# Phaser.net
KiCad netlist of a schematic drawn in Altium Designer
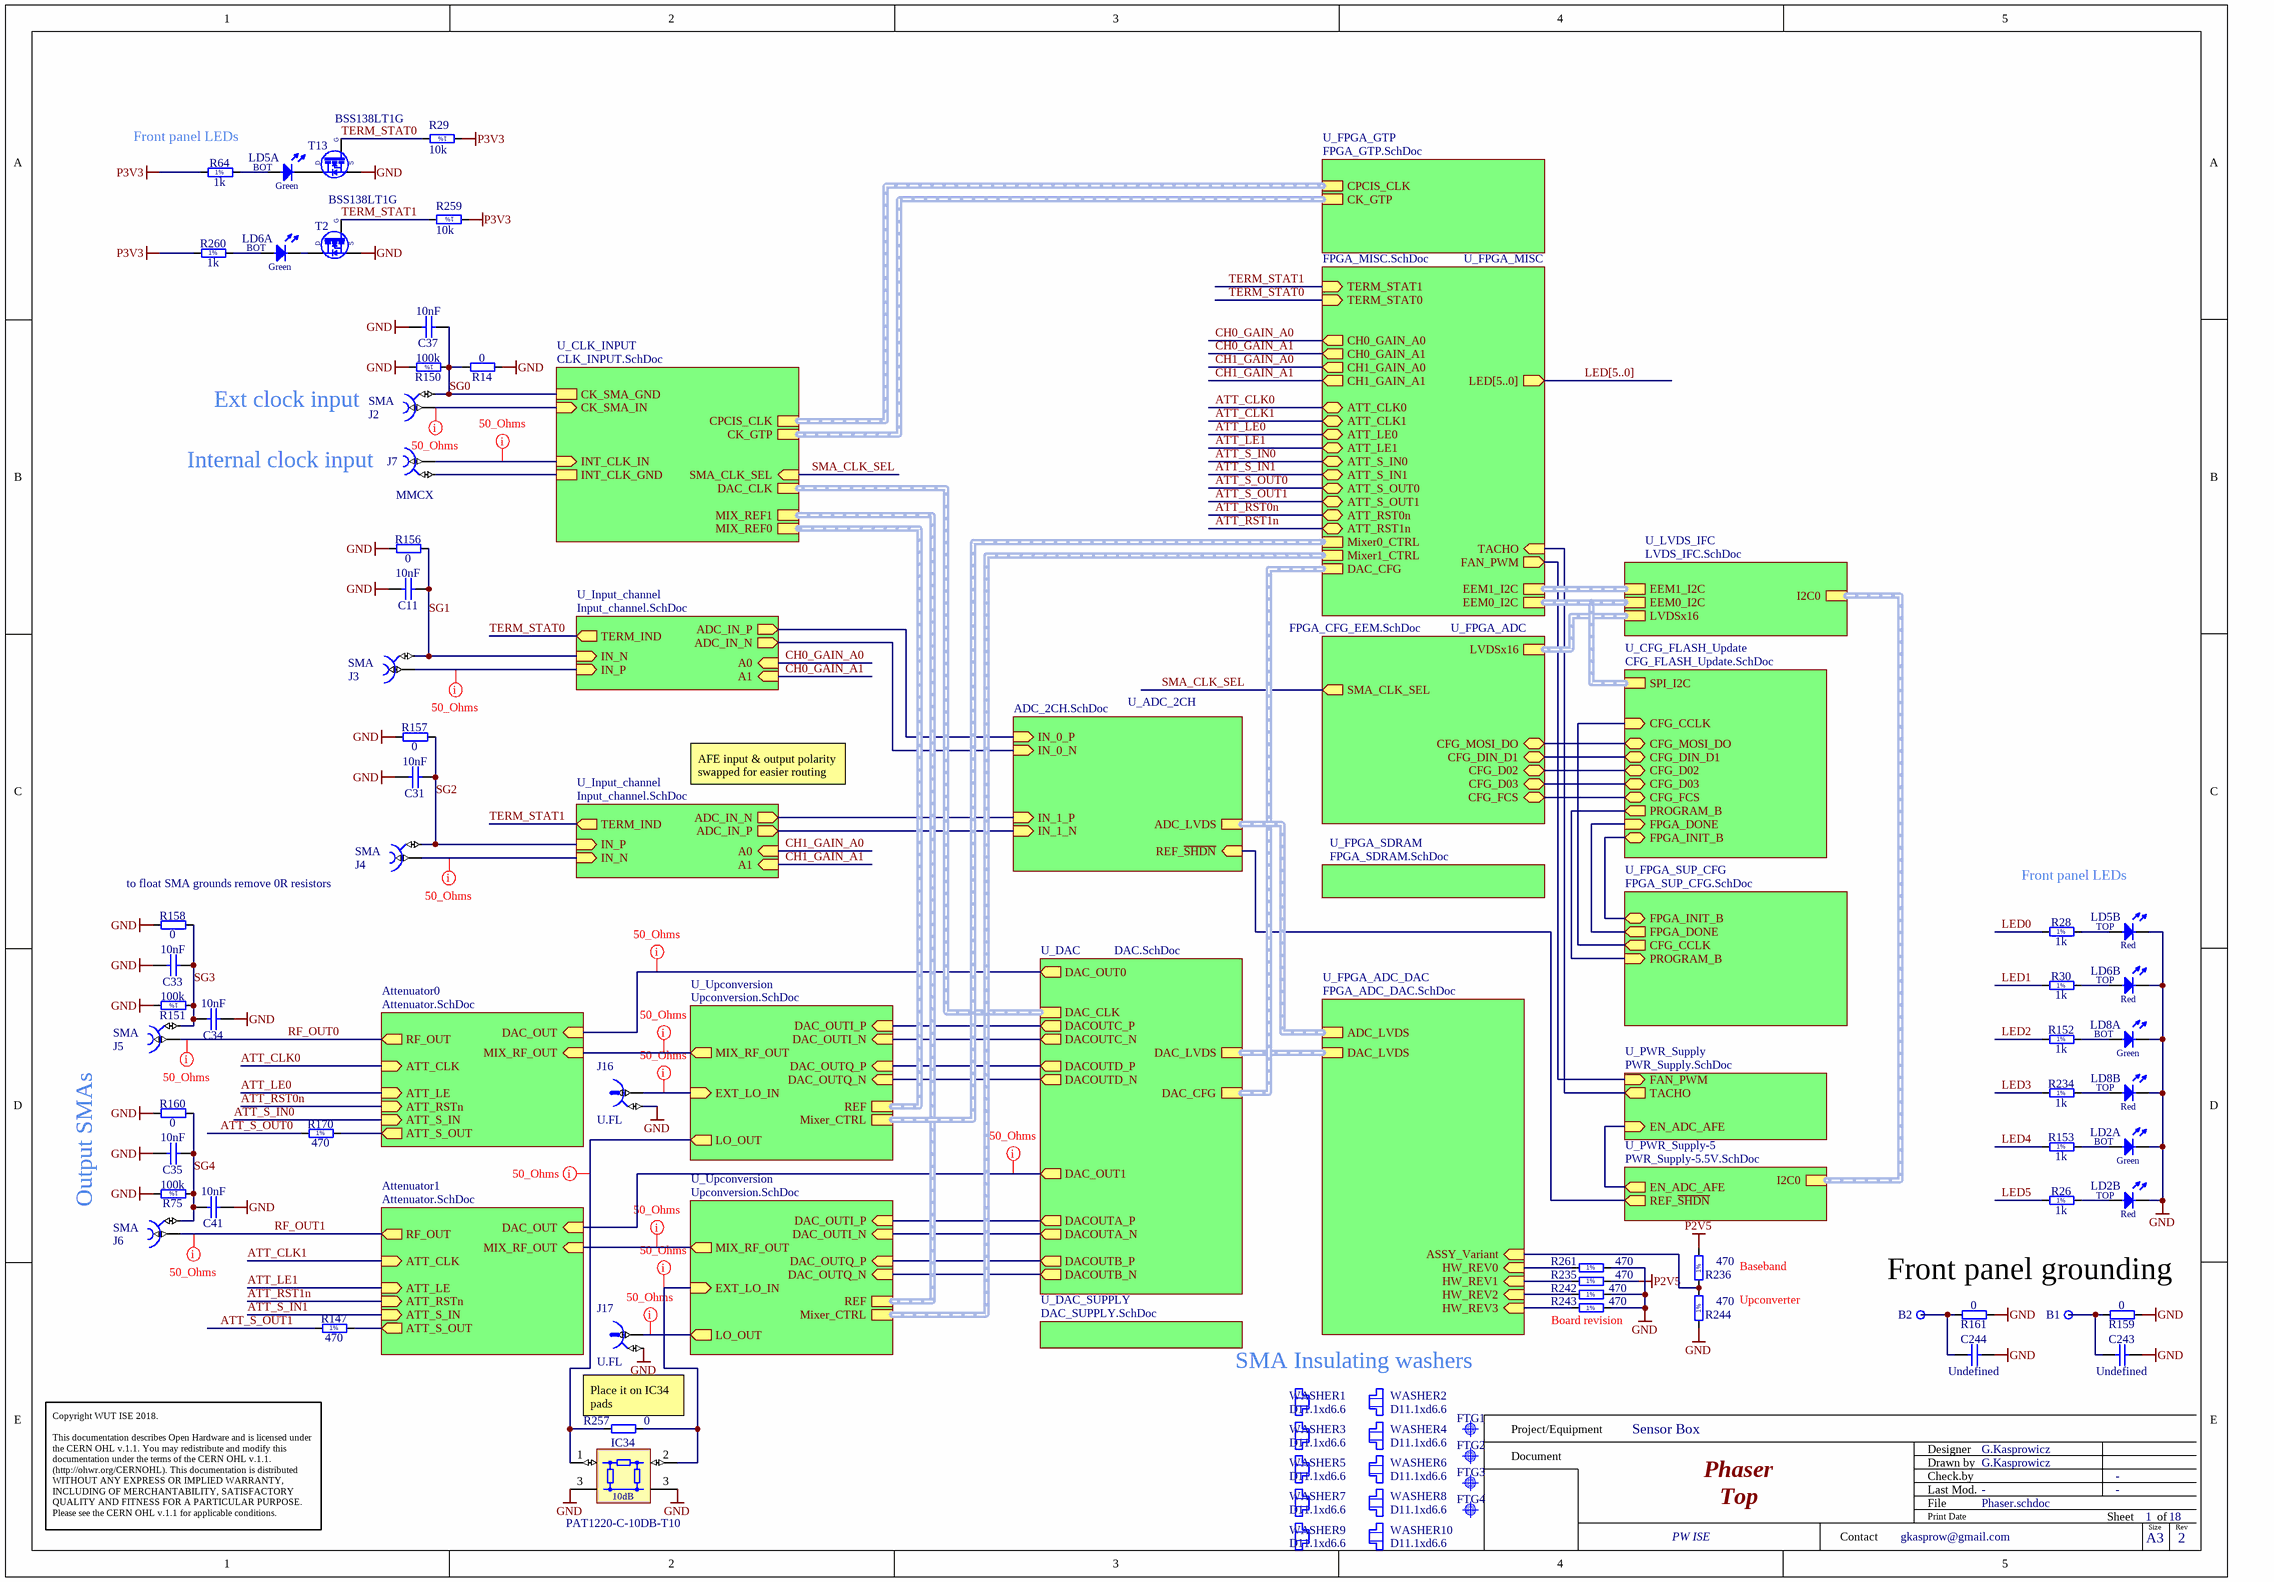
[diagram p0: Phaser.schdoc]

(export (version "E")
  (design (tool "Eeschema 10.0.6"))
  (components
    (comp (ref "B1")
      (value "Plated Hole")
      (footprint "MTG270_500")
      (description "Single Terminal Socket")
      (fields (field (name "PART NUMBER") "PLATED_HOLE2.7_PAD5.0") (field (name "AUTHOR") "CERN DEM JMW"))
      (libsource (lib "Eletro-mechanical") (part "Single Terminal Socket"))
    )
    (comp (ref "B2")
      (value "Plated Hole")
      (footprint "MTG270_500")
      (description "Single Terminal Socket")
      (fields (field (name "PART NUMBER") "PLATED_HOLE2.7_PAD5.0") (field (name "AUTHOR") "CERN DEM JMW"))
      (libsource (lib "Eletro-mechanical") (part "Single Terminal Socket"))
    )
    (comp (ref "C11")
      (value "10nF")
      (footprint "CAPC1005X55N")
      (description "Non-polarised capacitor")
      (fields
        (field (name "PART NUMBER") "CC0402_10NF_16V_10%_X7R")
        (field (name "VOLTAGE") "16V")
        (field (name "AUTHOR") "CERN DEM JLC")
      )
      (libsource (lib "Capacitors") (part "Capacitor - non polarized"))
    )
    (comp (ref "C31")
      (value "10nF")
      (footprint "CAPC1005X55N")
      (description "Non-polarised capacitor")
      (fields
        (field (name "PART NUMBER") "CC0402_10NF_16V_10%_X7R")
        (field (name "VOLTAGE") "16V")
        (field (name "AUTHOR") "CERN DEM JLC")
      )
      (libsource (lib "Capacitors") (part "Capacitor - non polarized"))
    )
    (comp (ref "C33")
      (value "10nF")
      (footprint "CAPC1005X55N")
      (description "Non-polarised capacitor")
      (fields
        (field (name "PART NUMBER") "CC0402_10NF_16V_10%_X7R")
        (field (name "VOLTAGE") "16V")
        (field (name "AUTHOR") "CERN DEM JLC")
      )
      (libsource (lib "Capacitors") (part "Capacitor - non polarized"))
    )
    (comp (ref "C34")
      (value "10nF")
      (footprint "CAPC1005X55N")
      (description "Non-polarised capacitor")
      (fields
        (field (name "PART NUMBER") "CC0402_10NF_16V_10%_X7R")
        (field (name "VOLTAGE") "16V")
        (field (name "AUTHOR") "CERN DEM JLC")
      )
      (libsource (lib "Capacitors") (part "Capacitor - non polarized"))
    )
    (comp (ref "C35")
      (value "10nF")
      (footprint "CAPC1005X55N")
      (description "Non-polarised capacitor")
      (fields
        (field (name "PART NUMBER") "CC0402_10NF_16V_10%_X7R")
        (field (name "VOLTAGE") "16V")
        (field (name "AUTHOR") "CERN DEM JLC")
      )
      (libsource (lib "Capacitors") (part "Capacitor - non polarized"))
    )
    (comp (ref "C37")
      (value "10nF")
      (footprint "CAPC1005X55N")
      (description "Non-polarised capacitor")
      (fields
        (field (name "PART NUMBER") "CC0402_10NF_16V_10%_X7R")
        (field (name "VOLTAGE") "16V")
        (field (name "AUTHOR") "CERN DEM JLC")
      )
      (libsource (lib "Capacitors") (part "Capacitor - non polarized"))
    )
    (comp (ref "C41")
      (value "10nF")
      (footprint "CAPC1005X55N")
      (description "Non-polarised capacitor")
      (fields
        (field (name "PART NUMBER") "CC0402_10NF_16V_10%_X7R")
        (field (name "VOLTAGE") "16V")
        (field (name "AUTHOR") "CERN DEM JLC")
      )
      (libsource (lib "Capacitors") (part "Capacitor - non polarized"))
    )
    (comp (ref "C243")
      (value "Undefined")
      (footprint "CAPC2012X135N")
      (description "Non-polarised capacitor")
      (fields (field (name "PART NUMBER") "CC0805_NO-VALUE") (field (name "AUTHOR") "CERN DEM JLC"))
      (libsource (lib "Capacitors") (part "Capacitor - non polarized"))
    )
    (comp (ref "C244")
      (value "Undefined")
      (footprint "CAPC2012X135N")
      (description "Non-polarised capacitor")
      (fields (field (name "PART NUMBER") "CC0805_NO-VALUE") (field (name "AUTHOR") "CERN DEM JLC"))
      (libsource (lib "Capacitors") (part "Capacitor - non polarized"))
    )
    (comp (ref "FTG1")
      (value "Use only in PCB")
      (footprint "FIDUCIAL_TOP_C100-200")
      (description "Fiducial Target")
      (fields (field (name "PART NUMBER") "FIDUCIAL_TARGET_C100-200") (field (name "AUTHOR") "CERN DEM JLC"))
      (libsource (lib "Eletro-mechanical") (part "Fiducial Target"))
    )
    (comp (ref "FTG2")
      (value "Use only in PCB")
      (footprint "FIDUCIAL_TOP_S100-200")
      (description "Fiducial Target")
      (fields (field (name "PART NUMBER") "FIDUCIAL_TARGET_S100-200") (field (name "AUTHOR") "CERN DEM JLC"))
      (libsource (lib "Eletro-mechanical") (part "Fiducial Target"))
    )
    (comp (ref "FTG3")
      (value "Use only in PCB")
      (footprint "FIDUCIAL_TOP_S100-200")
      (description "Fiducial Target")
      (fields (field (name "PART NUMBER") "FIDUCIAL_TARGET_S100-200") (field (name "AUTHOR") "CERN DEM JLC"))
      (libsource (lib "Eletro-mechanical") (part "Fiducial Target"))
    )
    (comp (ref "FTG4")
      (value "Use only in PCB")
      (footprint "FIDUCIAL_TOP_S100-200")
      (description "Fiducial Target")
      (fields (field (name "PART NUMBER") "FIDUCIAL_TARGET_S100-200") (field (name "AUTHOR") "CERN DEM JLC"))
      (libsource (lib "Eletro-mechanical") (part "Fiducial Target"))
    )
    (comp (ref "IC34")
      (value "PAT1220-C-10DB-T10")
      (footprint "SUSUMU_PAT1220")
      (description "DC to 10GHz, 100mW, 50 Ohm, 10dB, Precision Chip Attenuator")
      (fields (field (name "MANUFACTURER") "SUSUMU") (field (name "AUTHOR") "CERN DEM MR"))
      (libsource (lib "ICs And Semiconductors") (part "PAT1220-C-10DB"))
    )
    (comp (ref "J2")
      (value "SMA")
      (footprint "AMPHENOL_132203-14")
      (description "50 Ohm Through Hole SMA Right Angle PCB Jack")
      (fields
        (field (name "PART NUMBER") "AMPHENOL_132203-14")
        (field (name "MANUFACTURER") "AMPHENOL")
        (field (name "AUTHOR") "GK")
      )
      (libsource (lib "Connectors") (part "CON_SMA_AMP_132203-14"))
    )
    (comp (ref "J3")
      (value "SMA")
      (footprint "AMPHENOL_132203-14")
      (description "50 Ohm Through Hole SMA Right Angle PCB Jack")
      (fields
        (field (name "PART NUMBER") "AMPHENOL_132203-14")
        (field (name "MANUFACTURER") "AMPHENOL")
        (field (name "AUTHOR") "GK")
      )
      (libsource (lib "Connectors") (part "CON_SMA_AMP_132203-14"))
    )
    (comp (ref "J4")
      (value "SMA")
      (footprint "AMPHENOL_132203-14")
      (description "50 Ohm Through Hole SMA Right Angle PCB Jack")
      (fields
        (field (name "PART NUMBER") "AMPHENOL_132203-14")
        (field (name "MANUFACTURER") "AMPHENOL")
        (field (name "AUTHOR") "GK")
      )
      (libsource (lib "Connectors") (part "CON_SMA_AMP_132203-14"))
    )
    (comp (ref "J5")
      (value "SMA")
      (footprint "AMPHENOL_132203-14")
      (description "50 Ohm Through Hole SMA Right Angle PCB Jack")
      (fields
        (field (name "PART NUMBER") "AMPHENOL_132203-14")
        (field (name "MANUFACTURER") "AMPHENOL")
        (field (name "AUTHOR") "GK")
      )
      (libsource (lib "Connectors") (part "CON_SMA_AMP_132203-14"))
    )
    (comp (ref "J6")
      (value "SMA")
      (footprint "AMPHENOL_132203-14")
      (description "50 Ohm Through Hole SMA Right Angle PCB Jack")
      (fields
        (field (name "PART NUMBER") "AMPHENOL_132203-14")
        (field (name "MANUFACTURER") "AMPHENOL")
        (field (name "AUTHOR") "GK")
      )
      (libsource (lib "Connectors") (part "CON_SMA_AMP_132203-14"))
    )
    (comp (ref "J7")
      (value "MMCX")
      (footprint "SAMTEC_MMCX-J-P-H-ST-TH1")
      (fields
        (field (name "PART NUMBER") "SAMTEC_MMCX-J-P-H-ST-TH1")
        (field (name "MANUFACTURER") "SAMTEC")
        (field (name "MANUFACTURER PART NUMBER") "MMCX-J-P-H-ST-TH1")
        (field (name "AUTHOR") "CERN DEM JLC")
      )
      (libsource (lib "Connectors") (part "Coax_1Female_1Shield"))
    )
    (comp (ref "J16")
      (value "U.FL")
      (footprint "HIROSE_U.FL-R-SMT-1(10)")
      (fields
        (field (name "MANUFACTURER") "HIROSE (HRS)")
        (field (name "MANUFACTURER PART NUMBER") "U.FL-R-SMT-1(10)")
        (field (name "PART NUMBER") "HIROSE_U.FL-R-SMT-1(10)")
        (field (name "AUTHOR") "CERN DEM JLC")
      )
      (libsource (lib "Connectors") (part "Coax_1Male_1Shield"))
    )
    (comp (ref "J17")
      (value "U.FL")
      (footprint "HIROSE_U.FL-R-SMT-1(10)")
      (fields
        (field (name "MANUFACTURER") "HIROSE (HRS)")
        (field (name "MANUFACTURER PART NUMBER") "U.FL-R-SMT-1(10)")
        (field (name "PART NUMBER") "HIROSE_U.FL-R-SMT-1(10)")
        (field (name "AUTHOR") "CERN DEM JLC")
      )
      (libsource (lib "Connectors") (part "Coax_1Male_1Shield"))
    )
    (comp (ref "LD2")
      (value "Red/Green")
      (footprint "LED_DIALIGHT_571-0112F")
      (description "2x LED  Botom Green, Top Red")
      (fields
        (field (name "PART NUMBER") "LED_DIALIGHT_571-0112F")
        (field (name "MANUFACTURER") "DIALIGHT")
        (field (name "AUTHOR") "CERN DEM JLC")
      )
      (libsource (lib "ICs And Semiconductors") (part "LED x2 G-1C2A-BOT_R-3C4A-TOP"))
    )
    (comp (ref "LD5")
      (value "Red/Green")
      (footprint "LED_DIALIGHT_571-0112F")
      (description "2x LED  Botom Green, Top Red")
      (fields
        (field (name "PART NUMBER") "LED_DIALIGHT_571-0112F")
        (field (name "MANUFACTURER") "DIALIGHT")
        (field (name "AUTHOR") "CERN DEM JLC")
      )
      (libsource (lib "ICs And Semiconductors") (part "LED x2 G-1C2A-BOT_R-3C4A-TOP"))
    )
    (comp (ref "LD6")
      (value "Red/Green")
      (footprint "LED_DIALIGHT_571-0112F")
      (description "2x LED  Botom Green, Top Red")
      (fields
        (field (name "PART NUMBER") "LED_DIALIGHT_571-0112F")
        (field (name "MANUFACTURER") "DIALIGHT")
        (field (name "AUTHOR") "CERN DEM JLC")
      )
      (libsource (lib "ICs And Semiconductors") (part "LED x2 G-1C2A-BOT_R-3C4A-TOP"))
    )
    (comp (ref "LD8")
      (value "Red/Green")
      (footprint "LED_DIALIGHT_571-0112F")
      (description "2x LED  Botom Green, Top Red")
      (fields
        (field (name "PART NUMBER") "LED_DIALIGHT_571-0112F")
        (field (name "MANUFACTURER") "DIALIGHT")
        (field (name "AUTHOR") "CERN DEM JLC")
      )
      (libsource (lib "ICs And Semiconductors") (part "LED x2 G-1C2A-BOT_R-3C4A-TOP"))
    )
    (comp (ref "R14")
      (value "0")
      (footprint "RESC1608X55N")
      (description "Resistor")
      (fields
        (field (name "PART NUMBER") "R0603_0R_JUMPER")
        (field (name "MANUFACTURER") "GENERIC")
        (field (name "AUTHOR") "CERN DEM JLC")
      )
      (libsource (lib "Resistors") (part "Resistor"))
    )
    (comp (ref "R26")
      (value "1k")
      (footprint "RESC1005X40N")
      (description "Resistor - 1%")
      (fields
        (field (name "PART NUMBER") "R0402_1K_1%_0.0625W_100PPM")
        (field (name "POWER") "0.0625W")
        (field (name "AUTHOR") "CERN DEM JLC")
      )
      (libsource (lib "Resistors") (part "Resistor - 1%"))
    )
    (comp (ref "R28")
      (value "1k")
      (footprint "RESC1005X40N")
      (description "Resistor - 1%")
      (fields
        (field (name "PART NUMBER") "R0402_1K_1%_0.0625W_100PPM")
        (field (name "POWER") "0.0625W")
        (field (name "AUTHOR") "CERN DEM JLC")
      )
      (libsource (lib "Resistors") (part "Resistor - 1%"))
    )
    (comp (ref "R29")
      (value "10k")
      (footprint "RESC1005X40N")
      (description "Resistor - 1%")
      (fields
        (field (name "PART NUMBER") "R0402_10K_1%_0.0625W_100PPM")
        (field (name "POWER") "0.0625W")
        (field (name "AUTHOR") "CERN DEM JLC")
      )
      (libsource (lib "Resistors") (part "Resistor - 1%"))
    )
    (comp (ref "R30")
      (value "1k")
      (footprint "RESC1005X40N")
      (description "Resistor - 1%")
      (fields
        (field (name "PART NUMBER") "R0402_1K_1%_0.0625W_100PPM")
        (field (name "POWER") "0.0625W")
        (field (name "AUTHOR") "CERN DEM JLC")
      )
      (libsource (lib "Resistors") (part "Resistor - 1%"))
    )
    (comp (ref "R64")
      (value "1k")
      (footprint "RESC1005X40N")
      (description "Resistor - 1%")
      (fields
        (field (name "PART NUMBER") "R0402_1K_1%_0.0625W_100PPM")
        (field (name "POWER") "0.0625W")
        (field (name "AUTHOR") "CERN DEM JLC")
      )
      (libsource (lib "Resistors") (part "Resistor - 1%"))
    )
    (comp (ref "R75")
      (value "100k")
      (footprint "RESC1005X40N")
      (description "Resistor - 1%")
      (fields
        (field (name "PART NUMBER") "R0402_100K_1%_0.0625W_100PPM")
        (field (name "MANUFACTURER") "GENERIC")
        (field (name "AUTHOR") "CERN DEM JLC")
      )
      (libsource (lib "Resistors") (part "Resistor - 1%"))
    )
    (comp (ref "R147")
      (value "470")
      (footprint "RESC1005X40N")
      (description "Resistor - 1%")
      (fields
        (field (name "PART NUMBER") "R0402_470R_1%_0.0625W_100PPM")
        (field (name "POWER") "0.0625W")
        (field (name "AUTHOR") "CERN DEM JLC")
      )
      (libsource (lib "Resistors") (part "Resistor - 1%"))
    )
    (comp (ref "R150")
      (value "100k")
      (footprint "RESC1005X40N")
      (description "Resistor - 1%")
      (fields
        (field (name "PART NUMBER") "R0402_100K_1%_0.0625W_100PPM")
        (field (name "MANUFACTURER") "GENERIC")
        (field (name "AUTHOR") "CERN DEM JLC")
      )
      (libsource (lib "Resistors") (part "Resistor - 1%"))
    )
    (comp (ref "R151")
      (value "100k")
      (footprint "RESC1005X40N")
      (description "Resistor - 1%")
      (fields
        (field (name "PART NUMBER") "R0402_100K_1%_0.0625W_100PPM")
        (field (name "MANUFACTURER") "GENERIC")
        (field (name "AUTHOR") "CERN DEM JLC")
      )
      (libsource (lib "Resistors") (part "Resistor - 1%"))
    )
    (comp (ref "R152")
      (value "1k")
      (footprint "RESC1005X40N")
      (description "Resistor - 1%")
      (fields
        (field (name "PART NUMBER") "R0402_1K_1%_0.0625W_100PPM")
        (field (name "POWER") "0.0625W")
        (field (name "AUTHOR") "CERN DEM JLC")
      )
      (libsource (lib "Resistors") (part "Resistor - 1%"))
    )
    (comp (ref "R153")
      (value "1k")
      (footprint "RESC1005X40N")
      (description "Resistor - 1%")
      (fields
        (field (name "PART NUMBER") "R0402_1K_1%_0.0625W_100PPM")
        (field (name "POWER") "0.0625W")
        (field (name "AUTHOR") "CERN DEM JLC")
      )
      (libsource (lib "Resistors") (part "Resistor - 1%"))
    )
    (comp (ref "R156")
      (value "0")
      (footprint "RESC1608X55N")
      (description "Resistor")
      (fields
        (field (name "PART NUMBER") "R0603_0R_JUMPER")
        (field (name "MANUFACTURER") "GENERIC")
        (field (name "AUTHOR") "CERN DEM JLC")
      )
      (libsource (lib "Resistors") (part "Resistor"))
    )
    (comp (ref "R157")
      (value "0")
      (footprint "RESC1608X55N")
      (description "Resistor")
      (fields
        (field (name "PART NUMBER") "R0603_0R_JUMPER")
        (field (name "MANUFACTURER") "GENERIC")
        (field (name "AUTHOR") "CERN DEM JLC")
      )
      (libsource (lib "Resistors") (part "Resistor"))
    )
    (comp (ref "R158")
      (value "0")
      (footprint "RESC1608X55N")
      (description "Resistor")
      (fields
        (field (name "PART NUMBER") "R0603_0R_JUMPER")
        (field (name "MANUFACTURER") "GENERIC")
        (field (name "AUTHOR") "CERN DEM JLC")
      )
      (libsource (lib "Resistors") (part "Resistor"))
    )
    (comp (ref "R159")
      (value "0")
      (footprint "RESC1608X55N")
      (description "Resistor")
      (fields
        (field (name "PART NUMBER") "R0603_0R_JUMPER")
        (field (name "MANUFACTURER") "GENERIC")
        (field (name "AUTHOR") "CERN DEM JLC")
      )
      (libsource (lib "Resistors") (part "Resistor"))
    )
    (comp (ref "R160")
      (value "0")
      (footprint "RESC1608X55N")
      (description "Resistor")
      (fields
        (field (name "PART NUMBER") "R0603_0R_JUMPER")
        (field (name "MANUFACTURER") "GENERIC")
        (field (name "AUTHOR") "CERN DEM JLC")
      )
      (libsource (lib "Resistors") (part "Resistor"))
    )
    (comp (ref "R161")
      (value "0")
      (footprint "RESC1608X55N")
      (description "Resistor")
      (fields
        (field (name "PART NUMBER") "R0603_0R_JUMPER")
        (field (name "MANUFACTURER") "GENERIC")
        (field (name "AUTHOR") "CERN DEM JLC")
      )
      (libsource (lib "Resistors") (part "Resistor"))
    )
    (comp (ref "R170")
      (value "470")
      (footprint "RESC1005X40N")
      (description "Resistor - 1%")
      (fields
        (field (name "PART NUMBER") "R0402_470R_1%_0.0625W_100PPM")
        (field (name "POWER") "0.0625W")
        (field (name "AUTHOR") "CERN DEM JLC")
      )
      (libsource (lib "Resistors") (part "Resistor - 1%"))
    )
    (comp (ref "R234")
      (value "1k")
      (footprint "RESC1005X40N")
      (description "Resistor - 1%")
      (fields
        (field (name "PART NUMBER") "R0402_1K_1%_0.0625W_100PPM")
        (field (name "POWER") "0.0625W")
        (field (name "AUTHOR") "CERN DEM JLC")
      )
      (libsource (lib "Resistors") (part "Resistor - 1%"))
    )
    (comp (ref "R235")
      (value "470")
      (footprint "RESC1005X40N")
      (description "Resistor - 1%")
      (fields
        (field (name "PART NUMBER") "R0402_470R_1%_0.0625W_100PPM")
        (field (name "POWER") "0.0625W")
        (field (name "AUTHOR") "CERN DEM JLC")
      )
      (libsource (lib "Resistors") (part "Resistor - 1%"))
    )
    (comp (ref "R236")
      (value "470")
      (footprint "RESC1005X40N")
      (description "Resistor - 1%")
      (fields
        (field (name "PART NUMBER") "R0402_470R_1%_0.0625W_100PPM")
        (field (name "POWER") "0.0625W")
        (field (name "AUTHOR") "CERN DEM JLC")
      )
      (libsource (lib "Resistors") (part "Resistor - 1%"))
    )
    (comp (ref "R242")
      (value "470")
      (footprint "RESC1005X40N")
      (description "Resistor - 1%")
      (fields
        (field (name "PART NUMBER") "R0402_470R_1%_0.0625W_100PPM")
        (field (name "POWER") "0.0625W")
        (field (name "AUTHOR") "CERN DEM JLC")
      )
      (libsource (lib "Resistors") (part "Resistor - 1%"))
    )
    (comp (ref "R243")
      (value "470")
      (footprint "RESC1005X40N")
      (description "Resistor - 1%")
      (fields
        (field (name "PART NUMBER") "R0402_470R_1%_0.0625W_100PPM")
        (field (name "POWER") "0.0625W")
        (field (name "AUTHOR") "CERN DEM JLC")
      )
      (libsource (lib "Resistors") (part "Resistor - 1%"))
    )
    (comp (ref "R244")
      (value "470")
      (footprint "RESC1005X40N")
      (description "Resistor - 1%")
      (fields
        (field (name "PART NUMBER") "R0402_470R_1%_0.0625W_100PPM")
        (field (name "POWER") "0.0625W")
        (field (name "AUTHOR") "CERN DEM JLC")
      )
      (libsource (lib "Resistors") (part "Resistor - 1%"))
    )
    (comp (ref "R257")
      (value "0")
      (footprint "RESC1005X40N")
      (description "Resistor")
      (fields
        (field (name "PART NUMBER") "R0402_0R_JUMPER")
        (field (name "MANUFACTURER") "GENERIC")
        (field (name "AUTHOR") "CERN DEM JLC")
      )
      (libsource (lib "Resistors") (part "Resistor"))
    )
    (comp (ref "R259")
      (value "10k")
      (footprint "RESC1005X40N")
      (description "Resistor - 1%")
      (fields
        (field (name "PART NUMBER") "R0402_10K_1%_0.0625W_100PPM")
        (field (name "POWER") "0.0625W")
        (field (name "AUTHOR") "CERN DEM JLC")
      )
      (libsource (lib "Resistors") (part "Resistor - 1%"))
    )
    (comp (ref "R260")
      (value "1k")
      (footprint "RESC1005X40N")
      (description "Resistor - 1%")
      (fields
        (field (name "PART NUMBER") "R0402_1K_1%_0.0625W_100PPM")
        (field (name "POWER") "0.0625W")
        (field (name "AUTHOR") "CERN DEM JLC")
      )
      (libsource (lib "Resistors") (part "Resistor - 1%"))
    )
    (comp (ref "R261")
      (value "470")
      (footprint "RESC1005X40N")
      (description "Resistor - 1%")
      (fields
        (field (name "PART NUMBER") "R0402_470R_1%_0.0625W_100PPM")
        (field (name "POWER") "0.0625W")
        (field (name "AUTHOR") "CERN DEM JLC")
      )
      (libsource (lib "Resistors") (part "Resistor - 1%"))
    )
    (comp (ref "T2")
      (value "BSS138LT1G")
      (footprint "SOT95P240X110-3N")
      (description "N-CHANNEL MOSFET WITH DIODE")
      (fields (field (name "MANUFACTURER") "ON SEMICONDUCTOR") (field (name "AUTHOR") "CERN DEM JLC"))
      (libsource (lib "ICs And Semiconductors") (part "N-MOSFET-D 1G 2S 3D"))
    )
    (comp (ref "T13")
      (value "BSS138LT1G")
      (footprint "SOT95P240X110-3N")
      (description "N-CHANNEL MOSFET WITH DIODE")
      (fields (field (name "MANUFACTURER") "ON SEMICONDUCTOR") (field (name "AUTHOR") "CERN DEM JLC"))
      (libsource (lib "ICs And Semiconductors") (part "N-MOSFET-D 1G 2S 3D"))
    )
    (comp (ref "WASHER1")
      (value "D11.1xd6.6")
      (footprint "Keystone_7687")
      (description "SMA_Shoulder Washer")
      (fields (field (name "PART NUMBER") "custom 3D") (field (name "AUTHOR") "GK"))
      (libsource (lib "LIBRARY_SCH") (part "Keystone_7687"))
    )
    (comp (ref "WASHER2")
      (value "D11.1xd6.6")
      (footprint "Keystone_7687")
      (description "SMA_Shoulder Washer")
      (fields (field (name "PART NUMBER") "custom 3D") (field (name "AUTHOR") "GK"))
      (libsource (lib "LIBRARY_SCH") (part "Keystone_7687"))
    )
    (comp (ref "WASHER3")
      (value "D11.1xd6.6")
      (footprint "Keystone_7687")
      (description "SMA_Shoulder Washer")
      (fields (field (name "PART NUMBER") "custom 3D") (field (name "AUTHOR") "GK"))
      (libsource (lib "LIBRARY_SCH") (part "Keystone_7687"))
    )
    (comp (ref "WASHER4")
      (value "D11.1xd6.6")
      (footprint "Keystone_7687")
      (description "SMA_Shoulder Washer")
      (fields (field (name "PART NUMBER") "custom 3D") (field (name "AUTHOR") "GK"))
      (libsource (lib "LIBRARY_SCH") (part "Keystone_7687"))
    )
    (comp (ref "WASHER5")
      (value "D11.1xd6.6")
      (footprint "Keystone_7687")
      (description "SMA_Shoulder Washer")
      (fields (field (name "PART NUMBER") "custom 3D") (field (name "AUTHOR") "GK"))
      (libsource (lib "LIBRARY_SCH") (part "Keystone_7687"))
    )
    (comp (ref "WASHER6")
      (value "D11.1xd6.6")
      (footprint "Keystone_7687")
      (description "SMA_Shoulder Washer")
      (fields (field (name "PART NUMBER") "custom 3D") (field (name "AUTHOR") "GK"))
      (libsource (lib "LIBRARY_SCH") (part "Keystone_7687"))
    )
    (comp (ref "WASHER7")
      (value "D11.1xd6.6")
      (footprint "Keystone_7687")
      (description "SMA_Shoulder Washer")
      (fields (field (name "PART NUMBER") "custom 3D") (field (name "AUTHOR") "GK"))
      (libsource (lib "LIBRARY_SCH") (part "Keystone_7687"))
    )
    (comp (ref "WASHER8")
      (value "D11.1xd6.6")
      (footprint "Keystone_7687")
      (description "SMA_Shoulder Washer")
      (fields (field (name "PART NUMBER") "custom 3D") (field (name "AUTHOR") "GK"))
      (libsource (lib "LIBRARY_SCH") (part "Keystone_7687"))
    )
    (comp (ref "WASHER9")
      (value "D11.1xd6.6")
      (footprint "Keystone_7687")
      (description "SMA_Shoulder Washer")
      (fields (field (name "PART NUMBER") "custom 3D") (field (name "AUTHOR") "GK"))
      (libsource (lib "LIBRARY_SCH") (part "Keystone_7687"))
    )
    (comp (ref "WASHER10")
      (value "D11.1xd6.6")
      (footprint "Keystone_7687")
      (description "SMA_Shoulder Washer")
      (fields (field (name "PART NUMBER") "custom 3D") (field (name "AUTHOR") "GK"))
      (libsource (lib "LIBRARY_SCH") (part "Keystone_7687"))
    )
  )
  (nets
    (net (code "6") (name "/ASSY_Variant") (class "Default")
      (node (ref "R236") (pin "1") (pinfunction "1_1") (pintype "passive"))
      (node (ref "R244") (pin "2") (pinfunction "2_2") (pintype "passive"))
    )
    (net (code "15") (name "/ATT_S_OUT") (class "Default")
      (node (ref "R147") (pin "2") (pinfunction "2_2") (pintype "passive"))
    )
    (net (code "16") (name "/ATT_S_OUT0") (class "Default")
      (node (ref "R170") (pin "1") (pinfunction "1_1") (pintype "passive"))
    )
    (net (code "17") (name "/ATT_S_OUT1") (class "Default")
      (node (ref "R147") (pin "1") (pinfunction "1_1") (pintype "passive"))
    )
    (net (code "18") (name "/ATT_S_OUT_1") (class "Default")
      (node (ref "R170") (pin "2") (pinfunction "2_2") (pintype "passive"))
    )
    (net (code "30") (name "/CK_SMA_IN") (class "Default")
      (node (ref "J2") (pin "1") (pinfunction "1_1") (pintype "bidirectional"))
    )
    (net (code "48") (name "/EXT_LO_IN") (class "Default")
      (node (ref "IC34") (pin "2") (pinfunction "OUT_2") (pintype "bidirectional"))
      (node (ref "R257") (pin "1") (pinfunction "1_1") (pintype "passive"))
    )
    (net (code "49") (name "/EXT_LO_IN_1") (class "Default")
      (node (ref "J16") (pin "1") (pinfunction "1_1") (pintype "bidirectional"))
    )
    (net (code "53") (name "/HW_REV0") (class "Default")
      (node (ref "R261") (pin "1") (pinfunction "1_1") (pintype "passive"))
    )
    (net (code "54") (name "/HW_REV1") (class "Default")
      (node (ref "R235") (pin "1") (pinfunction "1_1") (pintype "passive"))
    )
    (net (code "55") (name "/HW_REV2") (class "Default")
      (node (ref "R242") (pin "1") (pinfunction "1_1") (pintype "passive"))
    )
    (net (code "56") (name "/HW_REV3") (class "Default")
      (node (ref "R243") (pin "1") (pinfunction "1_1") (pintype "passive"))
    )
    (net (code "58") (name "/INT_CLK_GND") (class "Default")
      (node (ref "J7") (pin "2") (pinfunction "2_2") (pintype "bidirectional"))
    )
    (net (code "59") (name "/INT_CLK_IN") (class "Default")
      (node (ref "J7") (pin "1") (pinfunction "1_1") (pintype "bidirectional"))
    )
    (net (code "60") (name "/IN_N") (class "Default")
      (node (ref "J4") (pin "1") (pinfunction "1_1") (pintype "bidirectional"))
    )
    (net (code "61") (name "/IN_P") (class "Default")
      (node (ref "J3") (pin "1") (pinfunction "1_1") (pintype "bidirectional"))
    )
    (net (code "62") (name "/LED0") (class "Default")
      (node (ref "R28") (pin "1") (pinfunction "1_1") (pintype "passive"))
    )
    (net (code "63") (name "/LED1") (class "Default")
      (node (ref "R30") (pin "1") (pinfunction "1_1") (pintype "passive"))
    )
    (net (code "64") (name "/LED2") (class "Default")
      (node (ref "R152") (pin "1") (pinfunction "1_1") (pintype "passive"))
    )
    (net (code "65") (name "/LED3") (class "Default")
      (node (ref "R234") (pin "1") (pinfunction "1_1") (pintype "passive"))
    )
    (net (code "66") (name "/LED4") (class "Default")
      (node (ref "R153") (pin "1") (pinfunction "1_1") (pintype "passive"))
    )
    (net (code "67") (name "/LED5") (class "Default")
      (node (ref "R26") (pin "1") (pinfunction "1_1") (pintype "passive"))
    )
    (net (code "69") (name "/LO_OUT") (class "Default")
      (node (ref "J17") (pin "1") (pinfunction "1_1") (pintype "bidirectional"))
    )
    (net (code "70") (name "/LO_OUT_1") (class "Default")
      (node (ref "IC34") (pin "1") (pinfunction "IN_1") (pintype "bidirectional"))
      (node (ref "R257") (pin "2") (pinfunction "2_2") (pintype "passive"))
    )
    (net (code "80") (name "/RF_OUT0") (class "Default")
      (node (ref "J5") (pin "1") (pinfunction "1_1") (pintype "bidirectional"))
    )
    (net (code "81") (name "/RF_OUT1") (class "Default")
      (node (ref "J6") (pin "1") (pinfunction "1_1") (pintype "bidirectional"))
    )
    (net (code "82") (name "/SG0") (class "Default")
      (node (ref "C37") (pin "1") (pinfunction "1_1") (pintype "passive"))
      (node (ref "J2") (pin "2") (pinfunction "2_2") (pintype "bidirectional"))
      (node (ref "R14") (pin "2") (pinfunction "2_2") (pintype "passive"))
      (node (ref "R150") (pin "2") (pinfunction "2_2") (pintype "passive"))
    )
    (net (code "83") (name "/SG1") (class "Default")
      (node (ref "C11") (pin "1") (pinfunction "1_1") (pintype "passive"))
      (node (ref "J3") (pin "2") (pinfunction "2_2") (pintype "bidirectional"))
      (node (ref "R156") (pin "2") (pinfunction "2_2") (pintype "passive"))
    )
    (net (code "84") (name "/SG2") (class "Default")
      (node (ref "C31") (pin "1") (pinfunction "1_1") (pintype "passive"))
      (node (ref "J4") (pin "2") (pinfunction "2_2") (pintype "bidirectional"))
      (node (ref "R157") (pin "2") (pinfunction "2_2") (pintype "passive"))
    )
    (net (code "85") (name "/SG3") (class "Default")
      (node (ref "C33") (pin "1") (pinfunction "1_1") (pintype "passive"))
      (node (ref "C34") (pin "2") (pinfunction "2_2") (pintype "passive"))
      (node (ref "J5") (pin "2") (pinfunction "2_2") (pintype "bidirectional"))
      (node (ref "R151") (pin "2") (pinfunction "2_2") (pintype "passive"))
      (node (ref "R158") (pin "2") (pinfunction "2_2") (pintype "passive"))
    )
    (net (code "86") (name "/SG4") (class "Default")
      (node (ref "C35") (pin "1") (pinfunction "1_1") (pintype "passive"))
      (node (ref "C41") (pin "2") (pinfunction "2_2") (pintype "passive"))
      (node (ref "J6") (pin "2") (pinfunction "2_2") (pintype "bidirectional"))
      (node (ref "R160") (pin "2") (pinfunction "2_2") (pintype "passive"))
      (node (ref "R75") (pin "2") (pinfunction "2_2") (pintype "passive"))
    )
    (net (code "89") (name "/TERM_STAT0") (class "Default")
      (node (ref "R29") (pin "2") (pinfunction "2_2") (pintype "passive"))
      (node (ref "T13") (pin "1") (pinfunction "G_1") (pintype "passive"))
    )
    (net (code "90") (name "/TERM_STAT1") (class "Default")
      (node (ref "R259") (pin "2") (pinfunction "2_2") (pintype "passive"))
      (node (ref "T2") (pin "1") (pinfunction "G_1") (pintype "passive"))
    )
    (net (code "91") (name "GND") (class "Default")
      (node (ref "C11") (pin "2") (pinfunction "2_2") (pintype "passive"))
      (node (ref "C243") (pin "2") (pinfunction "2_2") (pintype "passive"))
      (node (ref "C244") (pin "2") (pinfunction "2_2") (pintype "passive"))
      (node (ref "C31") (pin "2") (pinfunction "2_2") (pintype "passive"))
      (node (ref "C33") (pin "2") (pinfunction "2_2") (pintype "passive"))
      (node (ref "C34") (pin "1") (pinfunction "1_1") (pintype "passive"))
      (node (ref "C35") (pin "2") (pinfunction "2_2") (pintype "passive"))
      (node (ref "C37") (pin "2") (pinfunction "2_2") (pintype "passive"))
      (node (ref "C41") (pin "1") (pinfunction "1_1") (pintype "passive"))
      (node (ref "IC34") (pin "3") (pinfunction "GND_3") (pintype "passive"))
      (node (ref "J16") (pin "2") (pinfunction "2_2") (pintype "bidirectional"))
      (node (ref "J17") (pin "2") (pinfunction "2_2") (pintype "bidirectional"))
      (node (ref "LD2") (pin "1") (pinfunction "C_1") (pintype "passive"))
      (node (ref "LD2") (pin "3") (pinfunction "C_3") (pintype "passive"))
      (node (ref "LD5") (pin "3") (pinfunction "C_3") (pintype "passive"))
      (node (ref "LD6") (pin "3") (pinfunction "C_3") (pintype "passive"))
      (node (ref "LD8") (pin "1") (pinfunction "C_1") (pintype "passive"))
      (node (ref "LD8") (pin "3") (pinfunction "C_3") (pintype "passive"))
      (node (ref "R14") (pin "1") (pinfunction "1_1") (pintype "passive"))
      (node (ref "R150") (pin "1") (pinfunction "1_1") (pintype "passive"))
      (node (ref "R151") (pin "1") (pinfunction "1_1") (pintype "passive"))
      (node (ref "R156") (pin "1") (pinfunction "1_1") (pintype "passive"))
      (node (ref "R157") (pin "1") (pinfunction "1_1") (pintype "passive"))
      (node (ref "R158") (pin "1") (pinfunction "1_1") (pintype "passive"))
      (node (ref "R159") (pin "1") (pinfunction "1_1") (pintype "passive"))
      (node (ref "R160") (pin "1") (pinfunction "1_1") (pintype "passive"))
      (node (ref "R161") (pin "1") (pinfunction "1_1") (pintype "passive"))
      (node (ref "R242") (pin "2") (pinfunction "2_2") (pintype "passive"))
      (node (ref "R243") (pin "2") (pinfunction "2_2") (pintype "passive"))
      (node (ref "R244") (pin "1") (pinfunction "1_1") (pintype "passive"))
      (node (ref "R261") (pin "2") (pinfunction "2_2") (pintype "passive"))
      (node (ref "R75") (pin "1") (pinfunction "1_1") (pintype "passive"))
      (node (ref "T13") (pin "2") (pinfunction "S_2") (pintype "passive"))
      (node (ref "T2") (pin "2") (pinfunction "S_2") (pintype "passive"))
    )
    (net (code "92") (name "Net-(B1-Pad1)") (class "Default")
      (node (ref "B1") (pin "1") (pinfunction "1_1") (pintype "bidirectional"))
      (node (ref "C243") (pin "1") (pinfunction "1_1") (pintype "passive"))
      (node (ref "R159") (pin "2") (pinfunction "2_2") (pintype "passive"))
    )
    (net (code "93") (name "Net-(B2-Pad1)") (class "Default")
      (node (ref "B2") (pin "1") (pinfunction "1_1") (pintype "bidirectional"))
      (node (ref "C244") (pin "1") (pinfunction "1_1") (pintype "passive"))
      (node (ref "R161") (pin "2") (pinfunction "2_2") (pintype "passive"))
    )
    (net (code "94") (name "Net-(LD2A-A)") (class "Default")
      (node (ref "LD2") (pin "2") (pinfunction "A_2") (pintype "passive"))
      (node (ref "R153") (pin "2") (pinfunction "2_2") (pintype "passive"))
    )
    (net (code "95") (name "Net-(LD2B-A)") (class "Default")
      (node (ref "LD2") (pin "4") (pinfunction "A_4") (pintype "passive"))
      (node (ref "R26") (pin "2") (pinfunction "2_2") (pintype "passive"))
    )
    (net (code "96") (name "Net-(LD5A-A)") (class "Default")
      (node (ref "LD5") (pin "2") (pinfunction "A_2") (pintype "passive"))
      (node (ref "R64") (pin "2") (pinfunction "2_2") (pintype "passive"))
    )
    (net (code "97") (name "Net-(LD5A-C)") (class "Default")
      (node (ref "LD5") (pin "1") (pinfunction "C_1") (pintype "passive"))
      (node (ref "T13") (pin "3") (pinfunction "D_3") (pintype "passive"))
    )
    (net (code "98") (name "Net-(LD5B-A)") (class "Default")
      (node (ref "LD5") (pin "4") (pinfunction "A_4") (pintype "passive"))
      (node (ref "R28") (pin "2") (pinfunction "2_2") (pintype "passive"))
    )
    (net (code "99") (name "Net-(LD6A-A)") (class "Default")
      (node (ref "LD6") (pin "2") (pinfunction "A_2") (pintype "passive"))
      (node (ref "R260") (pin "2") (pinfunction "2_2") (pintype "passive"))
    )
    (net (code "100") (name "Net-(LD6A-C)") (class "Default")
      (node (ref "LD6") (pin "1") (pinfunction "C_1") (pintype "passive"))
      (node (ref "T2") (pin "3") (pinfunction "D_3") (pintype "passive"))
    )
    (net (code "101") (name "Net-(LD6B-A)") (class "Default")
      (node (ref "LD6") (pin "4") (pinfunction "A_4") (pintype "passive"))
      (node (ref "R30") (pin "2") (pinfunction "2_2") (pintype "passive"))
    )
    (net (code "102") (name "Net-(LD8A-A)") (class "Default")
      (node (ref "LD8") (pin "2") (pinfunction "A_2") (pintype "passive"))
      (node (ref "R152") (pin "2") (pinfunction "2_2") (pintype "passive"))
    )
    (net (code "103") (name "Net-(LD8B-A)") (class "Default")
      (node (ref "LD8") (pin "4") (pinfunction "A_4") (pintype "passive"))
      (node (ref "R234") (pin "2") (pinfunction "2_2") (pintype "passive"))
    )
    (net (code "104") (name "P2V5") (class "Default")
      (node (ref "R235") (pin "2") (pinfunction "2_2") (pintype "passive"))
      (node (ref "R236") (pin "2") (pinfunction "2_2") (pintype "passive"))
    )
    (net (code "105") (name "P3V3") (class "Default")
      (node (ref "R259") (pin "1") (pinfunction "1_1") (pintype "passive"))
      (node (ref "R260") (pin "1") (pinfunction "1_1") (pintype "passive"))
      (node (ref "R29") (pin "1") (pinfunction "1_1") (pintype "passive"))
      (node (ref "R64") (pin "1") (pinfunction "1_1") (pintype "passive"))
    )
  )
)
